# Laser_Array_Temp_Low_BRD_V2_0.net
KiCad netlist of a schematic drawn in EAGLE
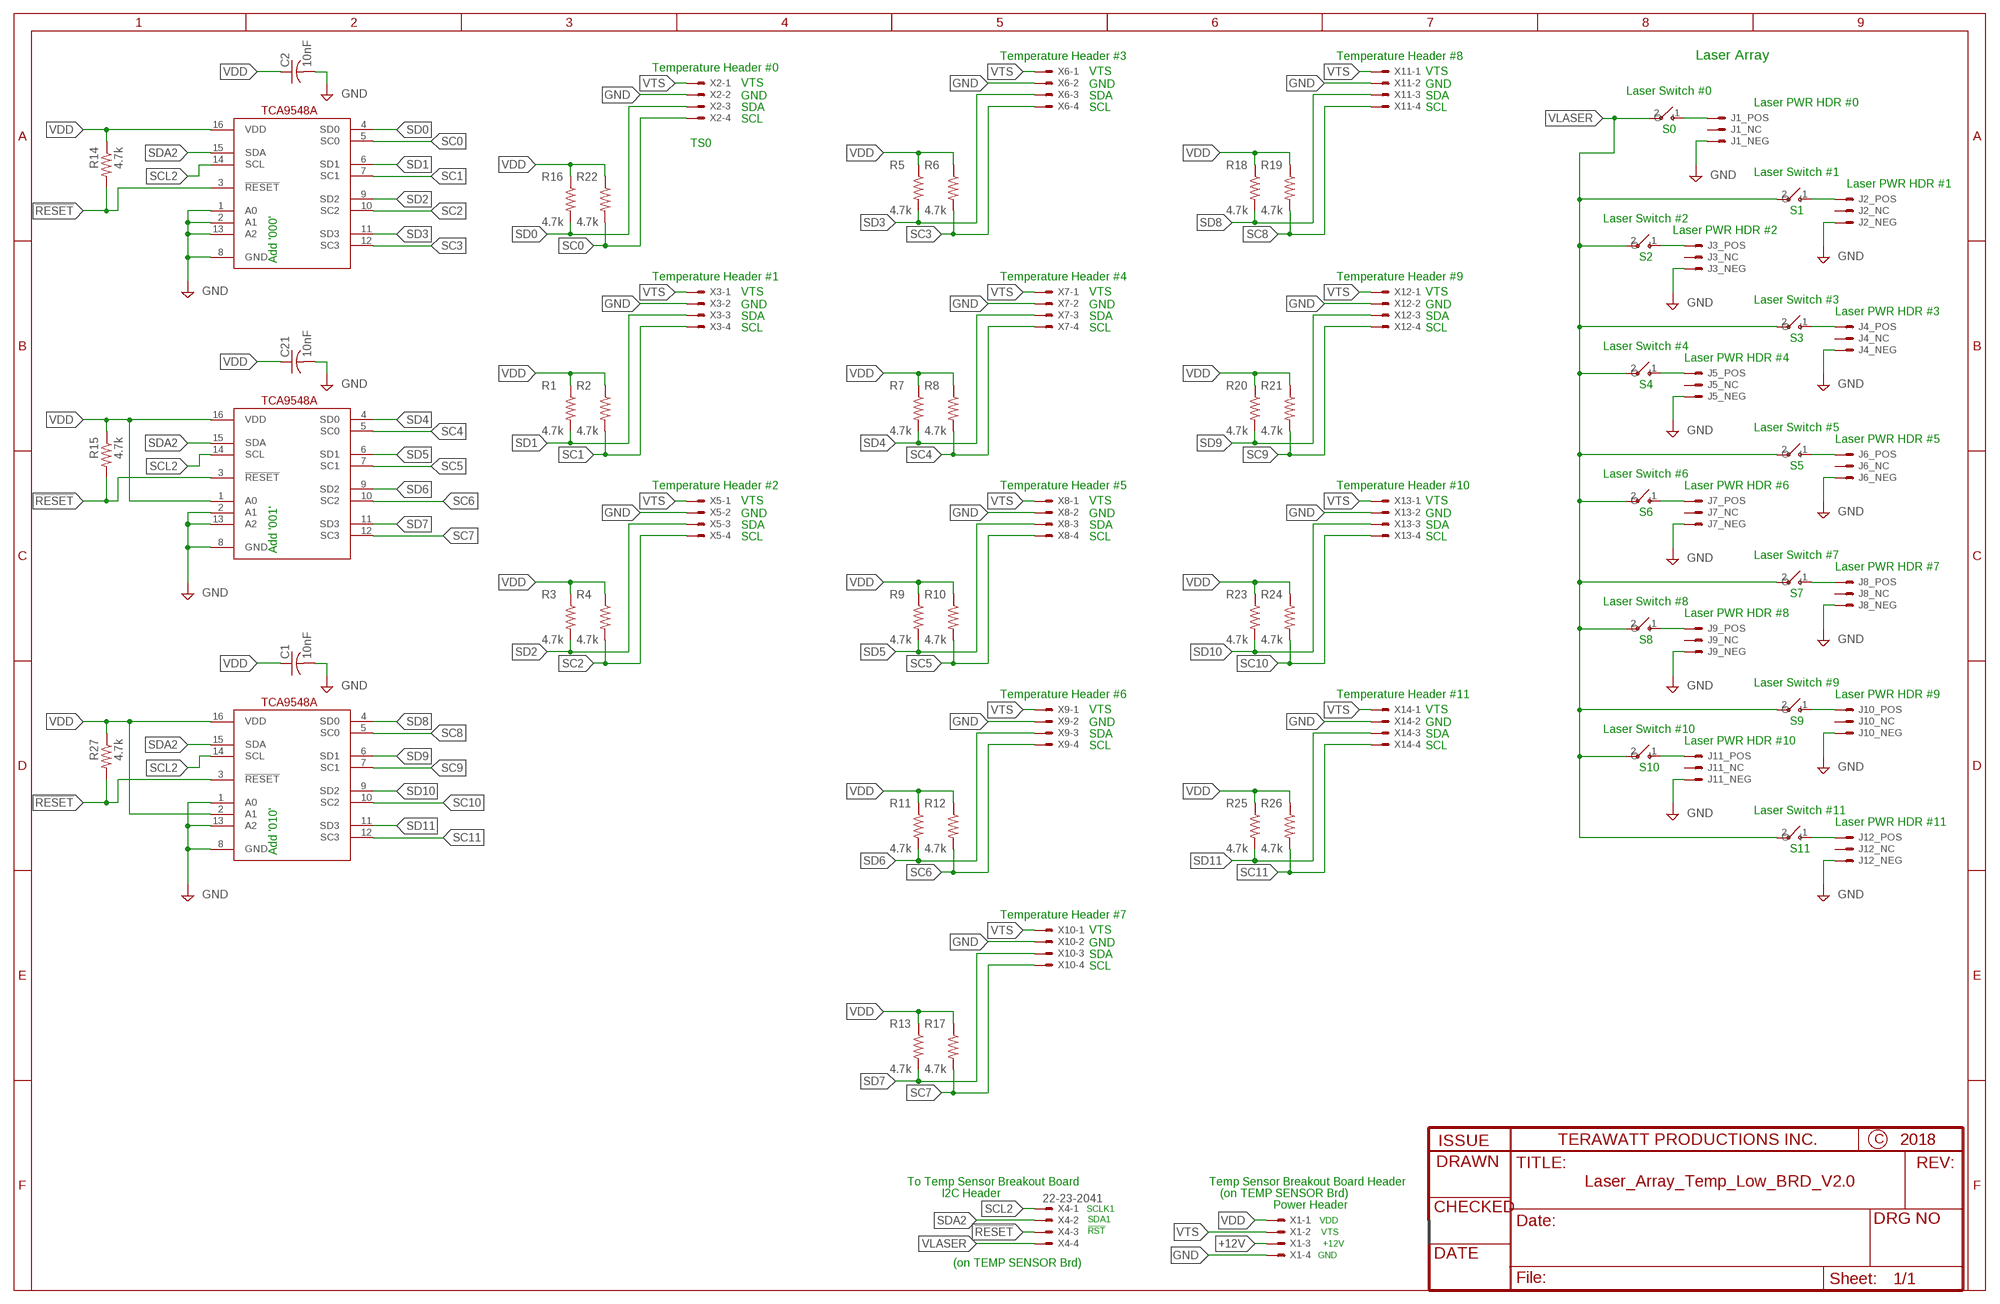
[diagram p0: schematic, sheet 1]

(export (version "E")
  (design (tool "Eeschema 10.0.6"))
  (components
    (comp (ref "C1")
      (value "10nF")
      (footprint "eagle-import:C0805")
      (libsource (lib "eagle-import") (part "C-USC0805"))
    )
    (comp (ref "C2")
      (value "10nF")
      (footprint "eagle-import:C0805")
      (libsource (lib "eagle-import") (part "C-USC0805"))
    )
    (comp (ref "C21")
      (value "10nF")
      (footprint "eagle-import:C0805")
      (libsource (lib "eagle-import") (part "C-USC0805"))
    )
    (comp (ref "J1")
      (value "LASER_MOD")
      (footprint "eagle-import:LASER_MOD")
      (libsource (lib "eagle-import") (part "LASER_MOD"))
    )
    (comp (ref "J2")
      (value "LASER_MOD")
      (footprint "eagle-import:LASER_MOD")
      (libsource (lib "eagle-import") (part "LASER_MOD"))
    )
    (comp (ref "J3")
      (value "LASER_MOD")
      (footprint "eagle-import:LASER_MOD")
      (libsource (lib "eagle-import") (part "LASER_MOD"))
    )
    (comp (ref "J4")
      (value "LASER_MOD")
      (footprint "eagle-import:LASER_MOD")
      (libsource (lib "eagle-import") (part "LASER_MOD"))
    )
    (comp (ref "J5")
      (value "LASER_MOD")
      (footprint "eagle-import:LASER_MOD")
      (libsource (lib "eagle-import") (part "LASER_MOD"))
    )
    (comp (ref "J6")
      (value "LASER_MOD")
      (footprint "eagle-import:LASER_MOD")
      (libsource (lib "eagle-import") (part "LASER_MOD"))
    )
    (comp (ref "J7")
      (value "LASER_MOD")
      (footprint "eagle-import:LASER_MOD")
      (libsource (lib "eagle-import") (part "LASER_MOD"))
    )
    (comp (ref "J8")
      (value "LASER_MOD")
      (footprint "eagle-import:LASER_MOD")
      (libsource (lib "eagle-import") (part "LASER_MOD"))
    )
    (comp (ref "J9")
      (value "LASER_MOD")
      (footprint "eagle-import:LASER_MOD")
      (libsource (lib "eagle-import") (part "LASER_MOD"))
    )
    (comp (ref "J10")
      (value "LASER_MOD")
      (footprint "eagle-import:LASER_MOD")
      (libsource (lib "eagle-import") (part "LASER_MOD"))
    )
    (comp (ref "J11")
      (value "LASER_MOD")
      (footprint "eagle-import:LASER_MOD")
      (libsource (lib "eagle-import") (part "LASER_MOD"))
    )
    (comp (ref "J12")
      (value "LASER_MOD")
      (footprint "eagle-import:LASER_MOD")
      (libsource (lib "eagle-import") (part "LASER_MOD"))
    )
    (comp (ref "R1")
      (value "4.7k")
      (footprint "eagle-import:M0805")
      (libsource (lib "eagle-import") (part "R-US_M0805"))
    )
    (comp (ref "R2")
      (value "4.7k")
      (footprint "eagle-import:M0805")
      (libsource (lib "eagle-import") (part "R-US_M0805"))
    )
    (comp (ref "R3")
      (value "4.7k")
      (footprint "eagle-import:M0805")
      (libsource (lib "eagle-import") (part "R-US_M0805"))
    )
    (comp (ref "R4")
      (value "4.7k")
      (footprint "eagle-import:M0805")
      (libsource (lib "eagle-import") (part "R-US_M0805"))
    )
    (comp (ref "R5")
      (value "4.7k")
      (footprint "eagle-import:M0805")
      (libsource (lib "eagle-import") (part "R-US_M0805"))
    )
    (comp (ref "R6")
      (value "4.7k")
      (footprint "eagle-import:M0805")
      (libsource (lib "eagle-import") (part "R-US_M0805"))
    )
    (comp (ref "R7")
      (value "4.7k")
      (footprint "eagle-import:M0805")
      (libsource (lib "eagle-import") (part "R-US_M0805"))
    )
    (comp (ref "R8")
      (value "4.7k")
      (footprint "eagle-import:M0805")
      (libsource (lib "eagle-import") (part "R-US_M0805"))
    )
    (comp (ref "R9")
      (value "4.7k")
      (footprint "eagle-import:M0805")
      (libsource (lib "eagle-import") (part "R-US_M0805"))
    )
    (comp (ref "R10")
      (value "4.7k")
      (footprint "eagle-import:M0805")
      (libsource (lib "eagle-import") (part "R-US_M0805"))
    )
    (comp (ref "R11")
      (value "4.7k")
      (footprint "eagle-import:M0805")
      (libsource (lib "eagle-import") (part "R-US_M0805"))
    )
    (comp (ref "R12")
      (value "4.7k")
      (footprint "eagle-import:M0805")
      (libsource (lib "eagle-import") (part "R-US_M0805"))
    )
    (comp (ref "R13")
      (value "4.7k")
      (footprint "eagle-import:M0805")
      (libsource (lib "eagle-import") (part "R-US_M0805"))
    )
    (comp (ref "R14")
      (value "4.7k")
      (footprint "eagle-import:M0805")
      (libsource (lib "eagle-import") (part "R-US_M0805"))
    )
    (comp (ref "R15")
      (value "4.7k")
      (footprint "eagle-import:M0805")
      (libsource (lib "eagle-import") (part "R-US_M0805"))
    )
    (comp (ref "R16")
      (value "4.7k")
      (footprint "eagle-import:M0805")
      (libsource (lib "eagle-import") (part "R-US_M0805"))
    )
    (comp (ref "R17")
      (value "4.7k")
      (footprint "eagle-import:M0805")
      (libsource (lib "eagle-import") (part "R-US_M0805"))
    )
    (comp (ref "R18")
      (value "4.7k")
      (footprint "eagle-import:M0805")
      (libsource (lib "eagle-import") (part "R-US_M0805"))
    )
    (comp (ref "R19")
      (value "4.7k")
      (footprint "eagle-import:M0805")
      (libsource (lib "eagle-import") (part "R-US_M0805"))
    )
    (comp (ref "R20")
      (value "4.7k")
      (footprint "eagle-import:M0805")
      (libsource (lib "eagle-import") (part "R-US_M0805"))
    )
    (comp (ref "R21")
      (value "4.7k")
      (footprint "eagle-import:M0805")
      (libsource (lib "eagle-import") (part "R-US_M0805"))
    )
    (comp (ref "R22")
      (value "4.7k")
      (footprint "eagle-import:M0805")
      (libsource (lib "eagle-import") (part "R-US_M0805"))
    )
    (comp (ref "R23")
      (value "4.7k")
      (footprint "eagle-import:M0805")
      (libsource (lib "eagle-import") (part "R-US_M0805"))
    )
    (comp (ref "R24")
      (value "4.7k")
      (footprint "eagle-import:M0805")
      (libsource (lib "eagle-import") (part "R-US_M0805"))
    )
    (comp (ref "R25")
      (value "4.7k")
      (footprint "eagle-import:M0805")
      (libsource (lib "eagle-import") (part "R-US_M0805"))
    )
    (comp (ref "R26")
      (value "4.7k")
      (footprint "eagle-import:M0805")
      (libsource (lib "eagle-import") (part "R-US_M0805"))
    )
    (comp (ref "R27")
      (value "4.7k")
      (footprint "eagle-import:M0805")
      (libsource (lib "eagle-import") (part "R-US_M0805"))
    )
    (comp (ref "S13")
      (value "TOGGLE_SPST")
      (footprint "eagle-import:22-23-2021")
      (libsource (lib "eagle-import") (part "TOGGLE_SPST"))
    )
    (comp (ref "S14")
      (value "TOGGLE_SPST")
      (footprint "eagle-import:22-23-2021")
      (libsource (lib "eagle-import") (part "TOGGLE_SPST"))
    )
    (comp (ref "S15")
      (value "TOGGLE_SPST")
      (footprint "eagle-import:22-23-2021")
      (libsource (lib "eagle-import") (part "TOGGLE_SPST"))
    )
    (comp (ref "S16")
      (value "TOGGLE_SPST")
      (footprint "eagle-import:22-23-2021")
      (libsource (lib "eagle-import") (part "TOGGLE_SPST"))
    )
    (comp (ref "S17")
      (value "TOGGLE_SPST")
      (footprint "eagle-import:22-23-2021")
      (libsource (lib "eagle-import") (part "TOGGLE_SPST"))
    )
    (comp (ref "S18")
      (value "TOGGLE_SPST")
      (footprint "eagle-import:22-23-2021")
      (libsource (lib "eagle-import") (part "TOGGLE_SPST"))
    )
    (comp (ref "S19")
      (value "TOGGLE_SPST")
      (footprint "eagle-import:22-23-2021")
      (libsource (lib "eagle-import") (part "TOGGLE_SPST"))
    )
    (comp (ref "S20")
      (value "TOGGLE_SPST")
      (footprint "eagle-import:22-23-2021")
      (libsource (lib "eagle-import") (part "TOGGLE_SPST"))
    )
    (comp (ref "S21")
      (value "TOGGLE_SPST")
      (footprint "eagle-import:22-23-2021")
      (libsource (lib "eagle-import") (part "TOGGLE_SPST"))
    )
    (comp (ref "S22")
      (value "TOGGLE_SPST")
      (footprint "eagle-import:22-23-2021")
      (libsource (lib "eagle-import") (part "TOGGLE_SPST"))
    )
    (comp (ref "S23")
      (value "TOGGLE_SPST")
      (footprint "eagle-import:22-23-2021")
      (libsource (lib "eagle-import") (part "TOGGLE_SPST"))
    )
    (comp (ref "S24")
      (value "TOGGLE_SPST")
      (footprint "eagle-import:22-23-2021")
      (libsource (lib "eagle-import") (part "TOGGLE_SPST"))
    )
    (comp (ref "U1")
      (value "TCA9546A")
      (footprint "eagle-import:SOIC16N")
      (libsource (lib "eagle-import") (part "TCA9546A"))
    )
    (comp (ref "U2")
      (value "TCA9546A")
      (footprint "eagle-import:SOIC16N")
      (libsource (lib "eagle-import") (part "TCA9546A"))
    )
    (comp (ref "U3")
      (value "TCA9546A")
      (footprint "eagle-import:SOIC16N")
      (libsource (lib "eagle-import") (part "TCA9546A"))
    )
    (comp (ref "X1")
      (value "22-23-2041")
      (footprint "eagle-import:22-23-2041")
      (fields (field (name "MF") "MOLEX"))
      (libsource (lib "eagle-import") (part "22-23-2041"))
    )
    (comp (ref "X2")
      (value "22-23-2041")
      (footprint "eagle-import:22-23-2041")
      (fields (field (name "MF") "MOLEX"))
      (libsource (lib "eagle-import") (part "22-23-2041"))
    )
    (comp (ref "X3")
      (value "22-23-2041")
      (footprint "eagle-import:22-23-2041")
      (fields (field (name "MF") "MOLEX"))
      (libsource (lib "eagle-import") (part "22-23-2041"))
    )
    (comp (ref "X4")
      (value "22-23-2041")
      (footprint "eagle-import:22-23-2041")
      (fields (field (name "MF") "MOLEX"))
      (libsource (lib "eagle-import") (part "22-23-2041"))
    )
    (comp (ref "X5")
      (value "22-23-2041")
      (footprint "eagle-import:22-23-2041")
      (fields (field (name "MF") "MOLEX"))
      (libsource (lib "eagle-import") (part "22-23-2041"))
    )
    (comp (ref "X6")
      (value "22-23-2041")
      (footprint "eagle-import:22-23-2041")
      (fields (field (name "MF") "MOLEX"))
      (libsource (lib "eagle-import") (part "22-23-2041"))
    )
    (comp (ref "X7")
      (value "22-23-2041")
      (footprint "eagle-import:22-23-2041")
      (fields (field (name "MF") "MOLEX"))
      (libsource (lib "eagle-import") (part "22-23-2041"))
    )
    (comp (ref "X8")
      (value "22-23-2041")
      (footprint "eagle-import:22-23-2041")
      (fields (field (name "MF") "MOLEX"))
      (libsource (lib "eagle-import") (part "22-23-2041"))
    )
    (comp (ref "X9")
      (value "22-23-2041")
      (footprint "eagle-import:22-23-2041")
      (fields (field (name "MF") "MOLEX"))
      (libsource (lib "eagle-import") (part "22-23-2041"))
    )
    (comp (ref "X10")
      (value "22-23-2041")
      (footprint "eagle-import:22-23-2041")
      (fields (field (name "MF") "MOLEX"))
      (libsource (lib "eagle-import") (part "22-23-2041"))
    )
    (comp (ref "X11")
      (value "22-23-2041")
      (footprint "eagle-import:22-23-2041")
      (fields (field (name "MF") "MOLEX"))
      (libsource (lib "eagle-import") (part "22-23-2041"))
    )
    (comp (ref "X12")
      (value "22-23-2041")
      (footprint "eagle-import:22-23-2041")
      (fields (field (name "MF") "MOLEX"))
      (libsource (lib "eagle-import") (part "22-23-2041"))
    )
    (comp (ref "X13")
      (value "22-23-2041")
      (footprint "eagle-import:22-23-2041")
      (fields (field (name "MF") "MOLEX"))
      (libsource (lib "eagle-import") (part "22-23-2041"))
    )
    (comp (ref "X14")
      (value "22-23-2041")
      (footprint "eagle-import:22-23-2041")
      (fields (field (name "MF") "MOLEX"))
      (libsource (lib "eagle-import") (part "22-23-2041"))
    )
  )
  (nets
    (net (code "1") (name "+12V") (class "Default")
      (node (ref "X1") (pin "3") (pinfunction "S_3") (pintype "passive"))
    )
    (net (code "2") (name "/~{RESET}") (class "Default")
      (node (ref "R14") (pin "2") (pinfunction "2_2") (pintype "passive"))
      (node (ref "R15") (pin "2") (pinfunction "2_2") (pintype "passive"))
      (node (ref "R27") (pin "2") (pinfunction "2_2") (pintype "passive"))
      (node (ref "U1") (pin "3") (pinfunction "~{RESET}_3") (pintype "bidirectional"))
      (node (ref "U2") (pin "3") (pinfunction "~{RESET}_3") (pintype "bidirectional"))
      (node (ref "U3") (pin "3") (pinfunction "~{RESET}_3") (pintype "bidirectional"))
      (node (ref "X4") (pin "3") (pinfunction "S_3") (pintype "passive"))
    )
    (net (code "3") (name "GND") (class "Default")
      (node (ref "C1") (pin "2") (pinfunction "2_2") (pintype "passive"))
      (node (ref "C2") (pin "2") (pinfunction "2_2") (pintype "passive"))
      (node (ref "C21") (pin "2") (pinfunction "2_2") (pintype "passive"))
      (node (ref "J1") (pin "3") (pinfunction "S_3") (pintype "passive"))
      (node (ref "J10") (pin "3") (pinfunction "S_3") (pintype "passive"))
      (node (ref "J11") (pin "3") (pinfunction "S_3") (pintype "passive"))
      (node (ref "J12") (pin "3") (pinfunction "S_3") (pintype "passive"))
      (node (ref "J2") (pin "3") (pinfunction "S_3") (pintype "passive"))
      (node (ref "J3") (pin "3") (pinfunction "S_3") (pintype "passive"))
      (node (ref "J4") (pin "3") (pinfunction "S_3") (pintype "passive"))
      (node (ref "J5") (pin "3") (pinfunction "S_3") (pintype "passive"))
      (node (ref "J6") (pin "3") (pinfunction "S_3") (pintype "passive"))
      (node (ref "J7") (pin "3") (pinfunction "S_3") (pintype "passive"))
      (node (ref "J8") (pin "3") (pinfunction "S_3") (pintype "passive"))
      (node (ref "J9") (pin "3") (pinfunction "S_3") (pintype "passive"))
      (node (ref "U1") (pin "1") (pinfunction "A0_1") (pintype "bidirectional"))
      (node (ref "U1") (pin "13") (pinfunction "A2_13") (pintype "bidirectional"))
      (node (ref "U1") (pin "2") (pinfunction "A1_2") (pintype "bidirectional"))
      (node (ref "U1") (pin "8") (pinfunction "GND_8") (pintype "bidirectional"))
      (node (ref "U2") (pin "13") (pinfunction "A2_13") (pintype "bidirectional"))
      (node (ref "U2") (pin "2") (pinfunction "A1_2") (pintype "bidirectional"))
      (node (ref "U2") (pin "8") (pinfunction "GND_8") (pintype "bidirectional"))
      (node (ref "U3") (pin "1") (pinfunction "A0_1") (pintype "bidirectional"))
      (node (ref "U3") (pin "13") (pinfunction "A2_13") (pintype "bidirectional"))
      (node (ref "U3") (pin "8") (pinfunction "GND_8") (pintype "bidirectional"))
      (node (ref "X1") (pin "4") (pinfunction "S_4") (pintype "passive"))
      (node (ref "X10") (pin "2") (pinfunction "S_2") (pintype "passive"))
      (node (ref "X11") (pin "2") (pinfunction "S_2") (pintype "passive"))
      (node (ref "X12") (pin "2") (pinfunction "S_2") (pintype "passive"))
      (node (ref "X13") (pin "2") (pinfunction "S_2") (pintype "passive"))
      (node (ref "X14") (pin "2") (pinfunction "S_2") (pintype "passive"))
      (node (ref "X2") (pin "2") (pinfunction "S_2") (pintype "passive"))
      (node (ref "X3") (pin "2") (pinfunction "S_2") (pintype "passive"))
      (node (ref "X5") (pin "2") (pinfunction "S_2") (pintype "passive"))
      (node (ref "X6") (pin "2") (pinfunction "S_2") (pintype "passive"))
      (node (ref "X7") (pin "2") (pinfunction "S_2") (pintype "passive"))
      (node (ref "X8") (pin "2") (pinfunction "S_2") (pintype "passive"))
      (node (ref "X9") (pin "2") (pinfunction "S_2") (pintype "passive"))
    )
    (net (code "4") (name "Net-(J1C-S)") (class "Default")
      (node (ref "J1") (pin "1") (pinfunction "S_1") (pintype "passive"))
      (node (ref "S16") (pin "1") (pinfunction "O_1") (pintype "bidirectional"))
    )
    (net (code "5") (name "Net-(J2C-S)") (class "Default")
      (node (ref "J2") (pin "1") (pinfunction "S_1") (pintype "passive"))
      (node (ref "S13") (pin "1") (pinfunction "O_1") (pintype "bidirectional"))
    )
    (net (code "6") (name "Net-(J3C-S)") (class "Default")
      (node (ref "J3") (pin "1") (pinfunction "S_1") (pintype "passive"))
      (node (ref "S14") (pin "1") (pinfunction "O_1") (pintype "bidirectional"))
    )
    (net (code "7") (name "Net-(J4C-S)") (class "Default")
      (node (ref "J4") (pin "1") (pinfunction "S_1") (pintype "passive"))
      (node (ref "S15") (pin "1") (pinfunction "O_1") (pintype "bidirectional"))
    )
    (net (code "8") (name "Net-(J5C-S)") (class "Default")
      (node (ref "J5") (pin "1") (pinfunction "S_1") (pintype "passive"))
      (node (ref "S17") (pin "1") (pinfunction "O_1") (pintype "bidirectional"))
    )
    (net (code "9") (name "Net-(J6C-S)") (class "Default")
      (node (ref "J6") (pin "1") (pinfunction "S_1") (pintype "passive"))
      (node (ref "S18") (pin "1") (pinfunction "O_1") (pintype "bidirectional"))
    )
    (net (code "10") (name "Net-(J7C-S)") (class "Default")
      (node (ref "J7") (pin "1") (pinfunction "S_1") (pintype "passive"))
      (node (ref "S19") (pin "1") (pinfunction "O_1") (pintype "bidirectional"))
    )
    (net (code "11") (name "Net-(J8C-S)") (class "Default")
      (node (ref "J8") (pin "1") (pinfunction "S_1") (pintype "passive"))
      (node (ref "S20") (pin "1") (pinfunction "O_1") (pintype "bidirectional"))
    )
    (net (code "12") (name "Net-(J9C-S)") (class "Default")
      (node (ref "J9") (pin "1") (pinfunction "S_1") (pintype "passive"))
      (node (ref "S21") (pin "1") (pinfunction "O_1") (pintype "bidirectional"))
    )
    (net (code "13") (name "Net-(J10C-S)") (class "Default")
      (node (ref "J10") (pin "1") (pinfunction "S_1") (pintype "passive"))
      (node (ref "S22") (pin "1") (pinfunction "O_1") (pintype "bidirectional"))
    )
    (net (code "14") (name "Net-(J11C-S)") (class "Default")
      (node (ref "J11") (pin "1") (pinfunction "S_1") (pintype "passive"))
      (node (ref "S23") (pin "1") (pinfunction "O_1") (pintype "bidirectional"))
    )
    (net (code "15") (name "Net-(J12C-S)") (class "Default")
      (node (ref "J12") (pin "1") (pinfunction "S_1") (pintype "passive"))
      (node (ref "S24") (pin "1") (pinfunction "O_1") (pintype "bidirectional"))
    )
    (net (code "16") (name "SC0") (class "Default")
      (node (ref "R22") (pin "2") (pinfunction "2_2") (pintype "passive"))
      (node (ref "U1") (pin "5") (pinfunction "SC0_5") (pintype "bidirectional"))
      (node (ref "X2") (pin "4") (pinfunction "S_4") (pintype "passive"))
    )
    (net (code "17") (name "SC1") (class "Default")
      (node (ref "R2") (pin "2") (pinfunction "2_2") (pintype "passive"))
      (node (ref "U1") (pin "7") (pinfunction "SC1_7") (pintype "bidirectional"))
      (node (ref "X3") (pin "4") (pinfunction "S_4") (pintype "passive"))
    )
    (net (code "18") (name "SC2") (class "Default")
      (node (ref "R4") (pin "2") (pinfunction "2_2") (pintype "passive"))
      (node (ref "U1") (pin "10") (pinfunction "SC2_10") (pintype "bidirectional"))
      (node (ref "X5") (pin "4") (pinfunction "S_4") (pintype "passive"))
    )
    (net (code "19") (name "SC3") (class "Default")
      (node (ref "R6") (pin "2") (pinfunction "2_2") (pintype "passive"))
      (node (ref "U1") (pin "12") (pinfunction "SC3_12") (pintype "bidirectional"))
      (node (ref "X6") (pin "4") (pinfunction "S_4") (pintype "passive"))
    )
    (net (code "20") (name "SC4") (class "Default")
      (node (ref "R8") (pin "2") (pinfunction "2_2") (pintype "passive"))
      (node (ref "U2") (pin "5") (pinfunction "SC0_5") (pintype "bidirectional"))
      (node (ref "X7") (pin "4") (pinfunction "S_4") (pintype "passive"))
    )
    (net (code "21") (name "SC5") (class "Default")
      (node (ref "R10") (pin "2") (pinfunction "2_2") (pintype "passive"))
      (node (ref "U2") (pin "7") (pinfunction "SC1_7") (pintype "bidirectional"))
      (node (ref "X8") (pin "4") (pinfunction "S_4") (pintype "passive"))
    )
    (net (code "22") (name "SC6") (class "Default")
      (node (ref "R12") (pin "2") (pinfunction "2_2") (pintype "passive"))
      (node (ref "U2") (pin "10") (pinfunction "SC2_10") (pintype "bidirectional"))
      (node (ref "X9") (pin "4") (pinfunction "S_4") (pintype "passive"))
    )
    (net (code "23") (name "SC7") (class "Default")
      (node (ref "R17") (pin "2") (pinfunction "2_2") (pintype "passive"))
      (node (ref "U2") (pin "12") (pinfunction "SC3_12") (pintype "bidirectional"))
      (node (ref "X10") (pin "4") (pinfunction "S_4") (pintype "passive"))
    )
    (net (code "24") (name "SC8") (class "Default")
      (node (ref "R19") (pin "2") (pinfunction "2_2") (pintype "passive"))
      (node (ref "U3") (pin "5") (pinfunction "SC0_5") (pintype "bidirectional"))
      (node (ref "X11") (pin "4") (pinfunction "S_4") (pintype "passive"))
    )
    (net (code "25") (name "SC9") (class "Default")
      (node (ref "R21") (pin "2") (pinfunction "2_2") (pintype "passive"))
      (node (ref "U3") (pin "7") (pinfunction "SC1_7") (pintype "bidirectional"))
      (node (ref "X12") (pin "4") (pinfunction "S_4") (pintype "passive"))
    )
    (net (code "26") (name "SC10") (class "Default")
      (node (ref "R24") (pin "2") (pinfunction "2_2") (pintype "passive"))
      (node (ref "U3") (pin "10") (pinfunction "SC2_10") (pintype "bidirectional"))
      (node (ref "X13") (pin "4") (pinfunction "S_4") (pintype "passive"))
    )
    (net (code "27") (name "SC11") (class "Default")
      (node (ref "R26") (pin "2") (pinfunction "2_2") (pintype "passive"))
      (node (ref "U3") (pin "12") (pinfunction "SC3_12") (pintype "bidirectional"))
      (node (ref "X14") (pin "4") (pinfunction "S_4") (pintype "passive"))
    )
    (net (code "28") (name "SCL2") (class "Default")
      (node (ref "U1") (pin "14") (pinfunction "SCL_14") (pintype "bidirectional"))
      (node (ref "U2") (pin "14") (pinfunction "SCL_14") (pintype "bidirectional"))
      (node (ref "U3") (pin "14") (pinfunction "SCL_14") (pintype "bidirectional"))
      (node (ref "X4") (pin "1") (pinfunction "S_1") (pintype "passive"))
    )
    (net (code "29") (name "SD0") (class "Default")
      (node (ref "R16") (pin "2") (pinfunction "2_2") (pintype "passive"))
      (node (ref "U1") (pin "4") (pinfunction "SD0_4") (pintype "bidirectional"))
      (node (ref "X2") (pin "3") (pinfunction "S_3") (pintype "passive"))
    )
    (net (code "30") (name "SD1") (class "Default")
      (node (ref "R1") (pin "2") (pinfunction "2_2") (pintype "passive"))
      (node (ref "U1") (pin "6") (pinfunction "SD1_6") (pintype "bidirectional"))
      (node (ref "X3") (pin "3") (pinfunction "S_3") (pintype "passive"))
    )
    (net (code "31") (name "SD2") (class "Default")
      (node (ref "R3") (pin "2") (pinfunction "2_2") (pintype "passive"))
      (node (ref "U1") (pin "9") (pinfunction "SD2_9") (pintype "bidirectional"))
      (node (ref "X5") (pin "3") (pinfunction "S_3") (pintype "passive"))
    )
    (net (code "32") (name "SD3") (class "Default")
      (node (ref "R5") (pin "2") (pinfunction "2_2") (pintype "passive"))
      (node (ref "U1") (pin "11") (pinfunction "SD3_11") (pintype "bidirectional"))
      (node (ref "X6") (pin "3") (pinfunction "S_3") (pintype "passive"))
    )
    (net (code "33") (name "SD4") (class "Default")
      (node (ref "R7") (pin "2") (pinfunction "2_2") (pintype "passive"))
      (node (ref "U2") (pin "4") (pinfunction "SD0_4") (pintype "bidirectional"))
      (node (ref "X7") (pin "3") (pinfunction "S_3") (pintype "passive"))
    )
    (net (code "34") (name "SD5") (class "Default")
      (node (ref "R9") (pin "2") (pinfunction "2_2") (pintype "passive"))
      (node (ref "U2") (pin "6") (pinfunction "SD1_6") (pintype "bidirectional"))
      (node (ref "X8") (pin "3") (pinfunction "S_3") (pintype "passive"))
    )
    (net (code "35") (name "SD6") (class "Default")
      (node (ref "R11") (pin "2") (pinfunction "2_2") (pintype "passive"))
      (node (ref "U2") (pin "9") (pinfunction "SD2_9") (pintype "bidirectional"))
      (node (ref "X9") (pin "3") (pinfunction "S_3") (pintype "passive"))
    )
    (net (code "36") (name "SD7") (class "Default")
      (node (ref "R13") (pin "2") (pinfunction "2_2") (pintype "passive"))
      (node (ref "U2") (pin "11") (pinfunction "SD3_11") (pintype "bidirectional"))
      (node (ref "X10") (pin "3") (pinfunction "S_3") (pintype "passive"))
    )
    (net (code "37") (name "SD8") (class "Default")
      (node (ref "R18") (pin "2") (pinfunction "2_2") (pintype "passive"))
      (node (ref "U3") (pin "4") (pinfunction "SD0_4") (pintype "bidirectional"))
      (node (ref "X11") (pin "3") (pinfunction "S_3") (pintype "passive"))
    )
    (net (code "38") (name "SD9") (class "Default")
      (node (ref "R20") (pin "2") (pinfunction "2_2") (pintype "passive"))
      (node (ref "U3") (pin "6") (pinfunction "SD1_6") (pintype "bidirectional"))
      (node (ref "X12") (pin "3") (pinfunction "S_3") (pintype "passive"))
    )
    (net (code "39") (name "SD10") (class "Default")
      (node (ref "R23") (pin "2") (pinfunction "2_2") (pintype "passive"))
      (node (ref "U3") (pin "9") (pinfunction "SD2_9") (pintype "bidirectional"))
      (node (ref "X13") (pin "3") (pinfunction "S_3") (pintype "passive"))
    )
    (net (code "40") (name "SD11") (class "Default")
      (node (ref "R25") (pin "2") (pinfunction "2_2") (pintype "passive"))
      (node (ref "U3") (pin "11") (pinfunction "SD3_11") (pintype "bidirectional"))
      (node (ref "X14") (pin "3") (pinfunction "S_3") (pintype "passive"))
    )
    (net (code "41") (name "SDA2") (class "Default")
      (node (ref "U1") (pin "15") (pinfunction "SDA_15") (pintype "bidirectional"))
      (node (ref "U2") (pin "15") (pinfunction "SDA_15") (pintype "bidirectional"))
      (node (ref "U3") (pin "15") (pinfunction "SDA_15") (pintype "bidirectional"))
      (node (ref "X4") (pin "2") (pinfunction "S_2") (pintype "passive"))
    )
    (net (code "42") (name "VDD") (class "Default")
      (node (ref "C1") (pin "1") (pinfunction "1_1") (pintype "passive"))
      (node (ref "C2") (pin "1") (pinfunction "1_1") (pintype "passive"))
      (node (ref "C21") (pin "1") (pinfunction "1_1") (pintype "passive"))
      (node (ref "R1") (pin "1") (pinfunction "1_1") (pintype "passive"))
      (node (ref "R10") (pin "1") (pinfunction "1_1") (pintype "passive"))
      (node (ref "R11") (pin "1") (pinfunction "1_1") (pintype "passive"))
      (node (ref "R12") (pin "1") (pinfunction "1_1") (pintype "passive"))
      (node (ref "R13") (pin "1") (pinfunction "1_1") (pintype "passive"))
      (node (ref "R14") (pin "1") (pinfunction "1_1") (pintype "passive"))
      (node (ref "R15") (pin "1") (pinfunction "1_1") (pintype "passive"))
      (node (ref "R16") (pin "1") (pinfunction "1_1") (pintype "passive"))
      (node (ref "R17") (pin "1") (pinfunction "1_1") (pintype "passive"))
      (node (ref "R18") (pin "1") (pinfunction "1_1") (pintype "passive"))
      (node (ref "R19") (pin "1") (pinfunction "1_1") (pintype "passive"))
      (node (ref "R2") (pin "1") (pinfunction "1_1") (pintype "passive"))
      (node (ref "R20") (pin "1") (pinfunction "1_1") (pintype "passive"))
      (node (ref "R21") (pin "1") (pinfunction "1_1") (pintype "passive"))
      (node (ref "R22") (pin "1") (pinfunction "1_1") (pintype "passive"))
      (node (ref "R23") (pin "1") (pinfunction "1_1") (pintype "passive"))
      (node (ref "R24") (pin "1") (pinfunction "1_1") (pintype "passive"))
      (node (ref "R25") (pin "1") (pinfunction "1_1") (pintype "passive"))
      (node (ref "R26") (pin "1") (pinfunction "1_1") (pintype "passive"))
      (node (ref "R27") (pin "1") (pinfunction "1_1") (pintype "passive"))
      (node (ref "R3") (pin "1") (pinfunction "1_1") (pintype "passive"))
      (node (ref "R4") (pin "1") (pinfunction "1_1") (pintype "passive"))
      (node (ref "R5") (pin "1") (pinfunction "1_1") (pintype "passive"))
      (node (ref "R6") (pin "1") (pinfunction "1_1") (pintype "passive"))
      (node (ref "R7") (pin "1") (pinfunction "1_1") (pintype "passive"))
      (node (ref "R8") (pin "1") (pinfunction "1_1") (pintype "passive"))
      (node (ref "R9") (pin "1") (pinfunction "1_1") (pintype "passive"))
      (node (ref "U1") (pin "16") (pinfunction "VDD_16") (pintype "bidirectional"))
      (node (ref "U2") (pin "1") (pinfunction "A0_1") (pintype "bidirectional"))
      (node (ref "U2") (pin "16") (pinfunction "VDD_16") (pintype "bidirectional"))
      (node (ref "U3") (pin "16") (pinfunction "VDD_16") (pintype "bidirectional"))
      (node (ref "U3") (pin "2") (pinfunction "A1_2") (pintype "bidirectional"))
      (node (ref "X1") (pin "1") (pinfunction "S_1") (pintype "passive"))
    )
    (net (code "43") (name "VLASER") (class "Default")
      (node (ref "S13") (pin "2") (pinfunction "I_2") (pintype "bidirectional"))
      (node (ref "S14") (pin "2") (pinfunction "I_2") (pintype "bidirectional"))
      (node (ref "S15") (pin "2") (pinfunction "I_2") (pintype "bidirectional"))
      (node (ref "S16") (pin "2") (pinfunction "I_2") (pintype "bidirectional"))
      (node (ref "S17") (pin "2") (pinfunction "I_2") (pintype "bidirectional"))
      (node (ref "S18") (pin "2") (pinfunction "I_2") (pintype "bidirectional"))
      (node (ref "S19") (pin "2") (pinfunction "I_2") (pintype "bidirectional"))
      (node (ref "S20") (pin "2") (pinfunction "I_2") (pintype "bidirectional"))
      (node (ref "S21") (pin "2") (pinfunction "I_2") (pintype "bidirectional"))
      (node (ref "S22") (pin "2") (pinfunction "I_2") (pintype "bidirectional"))
      (node (ref "S23") (pin "2") (pinfunction "I_2") (pintype "bidirectional"))
      (node (ref "S24") (pin "2") (pinfunction "I_2") (pintype "bidirectional"))
      (node (ref "X4") (pin "4") (pinfunction "S_4") (pintype "passive"))
    )
    (net (code "44") (name "VTS") (class "Default")
      (node (ref "X1") (pin "2") (pinfunction "S_2") (pintype "passive"))
      (node (ref "X10") (pin "1") (pinfunction "S_1") (pintype "passive"))
      (node (ref "X11") (pin "1") (pinfunction "S_1") (pintype "passive"))
      (node (ref "X12") (pin "1") (pinfunction "S_1") (pintype "passive"))
      (node (ref "X13") (pin "1") (pinfunction "S_1") (pintype "passive"))
      (node (ref "X14") (pin "1") (pinfunction "S_1") (pintype "passive"))
      (node (ref "X2") (pin "1") (pinfunction "S_1") (pintype "passive"))
      (node (ref "X3") (pin "1") (pinfunction "S_1") (pintype "passive"))
      (node (ref "X5") (pin "1") (pinfunction "S_1") (pintype "passive"))
      (node (ref "X6") (pin "1") (pinfunction "S_1") (pintype "passive"))
      (node (ref "X7") (pin "1") (pinfunction "S_1") (pintype "passive"))
      (node (ref "X8") (pin "1") (pinfunction "S_1") (pintype "passive"))
      (node (ref "X9") (pin "1") (pinfunction "S_1") (pintype "passive"))
    )
    (net (code "45") (name "unconnected-(J1A-S-Pad2)") (class "Default")
      (node (ref "J1") (pin "2") (pinfunction "S_2") (pintype "passive"))
    )
    (net (code "46") (name "unconnected-(J2A-S-Pad2)") (class "Default")
      (node (ref "J2") (pin "2") (pinfunction "S_2") (pintype "passive"))
    )
    (net (code "47") (name "unconnected-(J3A-S-Pad2)") (class "Default")
      (node (ref "J3") (pin "2") (pinfunction "S_2") (pintype "passive"))
    )
    (net (code "48") (name "unconnected-(J4A-S-Pad2)") (class "Default")
      (node (ref "J4") (pin "2") (pinfunction "S_2") (pintype "passive"))
    )
    (net (code "49") (name "unconnected-(J5A-S-Pad2)") (class "Default")
      (node (ref "J5") (pin "2") (pinfunction "S_2") (pintype "passive"))
    )
    (net (code "50") (name "unconnected-(J6A-S-Pad2)") (class "Default")
      (node (ref "J6") (pin "2") (pinfunction "S_2") (pintype "passive"))
    )
    (net (code "51") (name "unconnected-(J7A-S-Pad2)") (class "Default")
      (node (ref "J7") (pin "2") (pinfunction "S_2") (pintype "passive"))
    )
    (net (code "52") (name "unconnected-(J8A-S-Pad2)") (class "Default")
      (node (ref "J8") (pin "2") (pinfunction "S_2") (pintype "passive"))
    )
    (net (code "53") (name "unconnected-(J9A-S-Pad2)") (class "Default")
      (node (ref "J9") (pin "2") (pinfunction "S_2") (pintype "passive"))
    )
    (net (code "54") (name "unconnected-(J10A-S-Pad2)") (class "Default")
      (node (ref "J10") (pin "2") (pinfunction "S_2") (pintype "passive"))
    )
    (net (code "55") (name "unconnected-(J11A-S-Pad2)") (class "Default")
      (node (ref "J11") (pin "2") (pinfunction "S_2") (pintype "passive"))
    )
    (net (code "56") (name "unconnected-(J12A-S-Pad2)") (class "Default")
      (node (ref "J12") (pin "2") (pinfunction "S_2") (pintype "passive"))
    )
  )
)
